# Connectors.net
KiCad netlist of a schematic drawn in Altium Designer
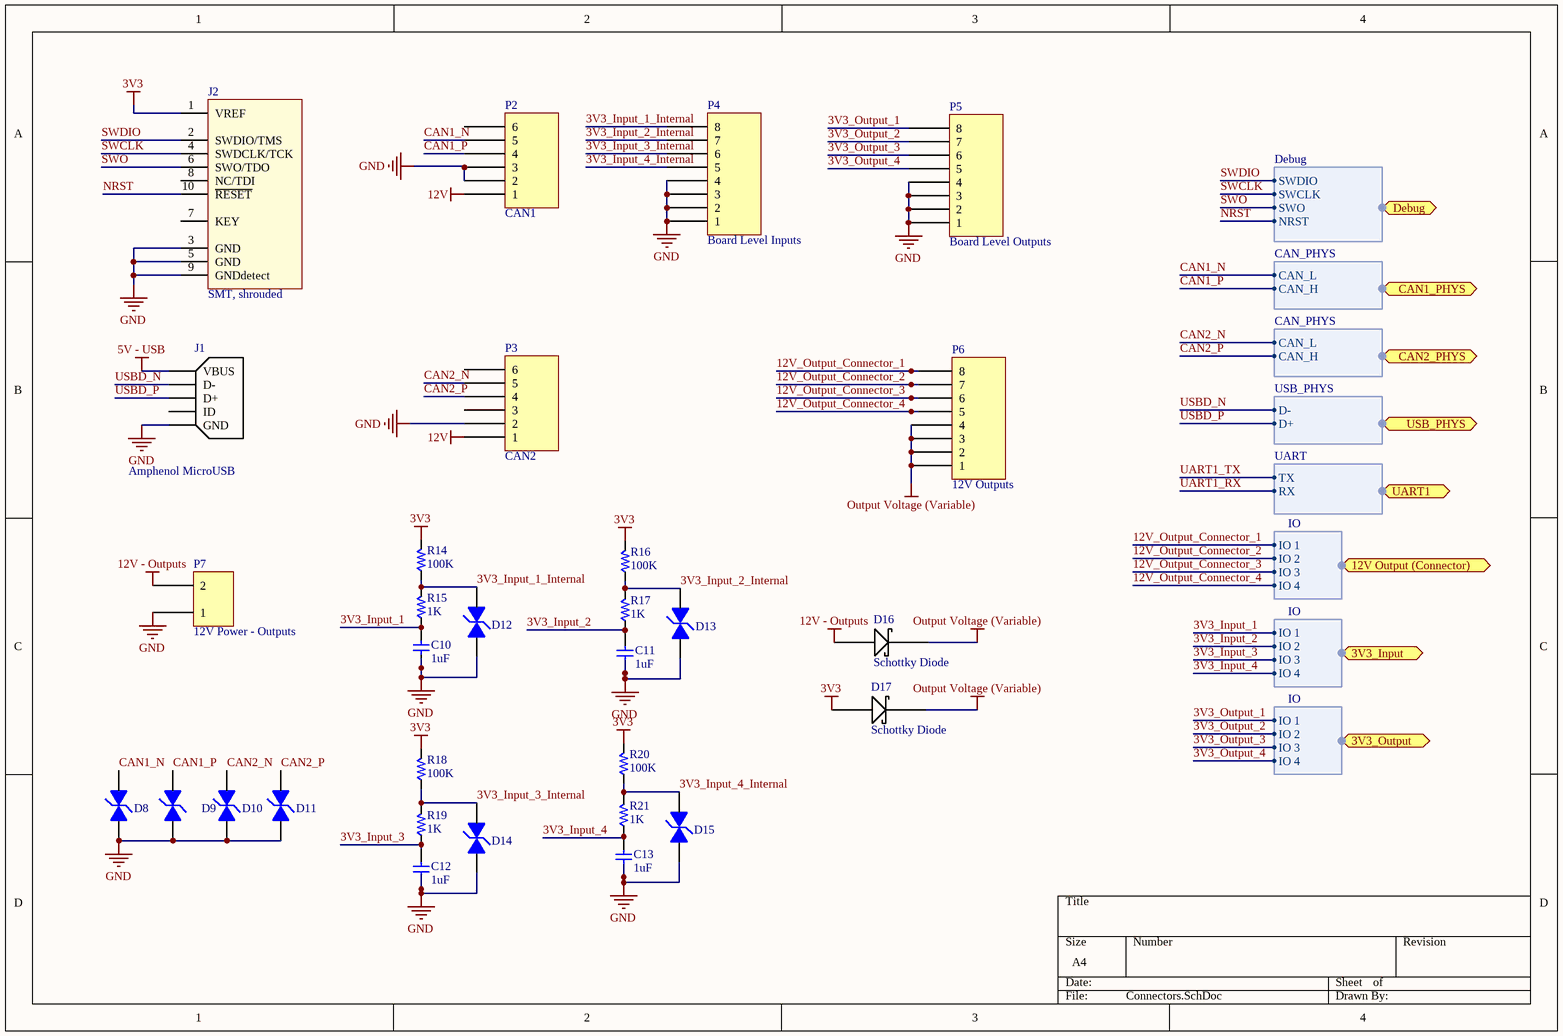
[diagram p0: Connectors.SchDoc]

(export (version "E")
  (design (tool "Eeschema 10.0.6"))
  (components
    (comp (ref "C10")
      (value "1uF")
      (footprint "PCB_GENERIC_SMD_0603")
      (description "CAP CER 0603 1uF 16V X5R 20%")
      (fields (field (name "TOLERANCE") "20%") (field (name "VOLTAGE") "16V"))
      (libsource (lib "CAP-0603") (part "C060-0001U-00"))
    )
    (comp (ref "C11")
      (value "1uF")
      (footprint "PCB_GENERIC_SMD_0603")
      (description "CAP CER 0603 1uF 16V X5R 20%")
      (fields (field (name "TOLERANCE") "20%") (field (name "VOLTAGE") "16V"))
      (libsource (lib "CAP-0603") (part "C060-0001U-00"))
    )
    (comp (ref "C12")
      (value "1uF")
      (footprint "PCB_GENERIC_SMD_0603")
      (description "CAP CER 0603 1uF 16V X5R 20%")
      (fields (field (name "TOLERANCE") "20%") (field (name "VOLTAGE") "16V"))
      (libsource (lib "CAP-0603") (part "C060-0001U-00"))
    )
    (comp (ref "C13")
      (value "1uF")
      (footprint "PCB_GENERIC_SMD_0603")
      (description "CAP CER 0603 1uF 16V X5R 20%")
      (fields (field (name "TOLERANCE") "20%") (field (name "VOLTAGE") "16V"))
      (libsource (lib "CAP-0603") (part "C060-0001U-00"))
    )
    (comp (ref "D8")
      (value "TVS Diode")
      (footprint "TVS Diode")
      (fields (field (name "MANUFACTURER") "Bourns"))
      (libsource (lib "TVS Diode") (part "TVS Diode"))
    )
    (comp (ref "D9")
      (value "TVS Diode")
      (footprint "TVS Diode")
      (fields (field (name "MANUFACTURER") "Bourns"))
      (libsource (lib "TVS Diode") (part "TVS Diode"))
    )
    (comp (ref "D10")
      (value "TVS Diode")
      (footprint "TVS Diode")
      (fields (field (name "MANUFACTURER") "Bourns"))
      (libsource (lib "TVS Diode") (part "TVS Diode"))
    )
    (comp (ref "D11")
      (value "TVS Diode")
      (footprint "TVS Diode")
      (fields (field (name "MANUFACTURER") "Bourns"))
      (libsource (lib "TVS Diode") (part "TVS Diode"))
    )
    (comp (ref "D12")
      (value "TVS Diode")
      (footprint "TVS Diode")
      (fields (field (name "MANUFACTURER") "Bourns"))
      (libsource (lib "TVS Diode") (part "TVS Diode"))
    )
    (comp (ref "D13")
      (value "TVS Diode")
      (footprint "TVS Diode")
      (fields (field (name "MANUFACTURER") "Bourns"))
      (libsource (lib "TVS Diode") (part "TVS Diode"))
    )
    (comp (ref "D14")
      (value "TVS Diode")
      (footprint "TVS Diode")
      (fields (field (name "MANUFACTURER") "Bourns"))
      (libsource (lib "TVS Diode") (part "TVS Diode"))
    )
    (comp (ref "D15")
      (value "TVS Diode")
      (footprint "TVS Diode")
      (fields (field (name "MANUFACTURER") "Bourns"))
      (libsource (lib "TVS Diode") (part "TVS Diode"))
    )
    (comp (ref "D16")
      (value "Schottky Diode")
      (footprint "ON Semi Schottky Diode - MBRM110LT1G")
      (libsource (lib "ON Semi Schottky Diode") (part "ON Semi Schottky Diode - MBRM110LT1G"))
    )
    (comp (ref "D17")
      (value "Schottky Diode")
      (footprint "ON Semi Schottky Diode - MBRM110LT1G")
      (libsource (lib "ON Semi Schottky Diode") (part "ON Semi Schottky Diode - MBRM110LT1G"))
    )
    (comp (ref "J1")
      (value "Amphenol MicroUSB")
      (footprint "Amphenol MicroUSB")
      (libsource (lib "Amphenol MicroUSB") (part "Amphenol MicroUSB - 609-4618-1-ND"))
    )
    (comp (ref "J2")
      (value "SMT, shrouded")
      (footprint "CONN-50mil-10POS-SMD")
      (description "ARM Cortex-M 10pin connector,shrouded,SMT")
      (libsource (lib "CONN-50mil-cortexM") (part "conn_0.050{dblquote}_cortexM"))
    )
    (comp (ref "P2")
      (value "CAN1")
      (footprint "Molex Microfit 3.0 3x2:PCB_MLX_MICROFIT_3X2")
      (libsource (lib "Molex Microfit 3.0 3x2") (part "SCH_MLX_MICROFIT_3X2"))
    )
    (comp (ref "P3")
      (value "CAN2")
      (footprint "Molex Microfit 3.0 3x2:PCB_MLX_MICROFIT_3X2")
      (libsource (lib "Molex Microfit 3.0 3x2") (part "SCH_MLX_MICROFIT_3X2"))
    )
    (comp (ref "P4")
      (value "Board Level Inputs")
      (footprint "Molex Microfit 3.0 4x2:PCB_MLX_MICROFIT_4X2")
      (description "Molex Microfit Connector 4x2")
      (libsource (lib "Molex Microfit 3.0 4x2") (part "SCH_MLX_MICROFIT_4X2"))
    )
    (comp (ref "P5")
      (value "Board Level Outputs")
      (footprint "Molex Microfit 3.0 4x2:PCB_MLX_MICROFIT_4X2")
      (description "Molex Microfit Connector 4x2")
      (libsource (lib "Molex Microfit 3.0 4x2") (part "SCH_MLX_MICROFIT_4X2"))
    )
    (comp (ref "P6")
      (value "12V Outputs")
      (footprint "Molex Microfit 3.0 4x2:PCB_MLX_MICROFIT_4X2")
      (description "Molex Microfit Connector 4x2")
      (libsource (lib "Molex Microfit 3.0 4x2") (part "SCH_MLX_MICROFIT_4X2"))
    )
    (comp (ref "P7")
      (value "12V Power - Outputs")
      (footprint "Molex Mini-Fit Jr 2x1")
      (libsource (lib "Molex Mini-Fit Jr 1x2") (part "Molex Mini-Fit 1x2"))
    )
    (comp (ref "R14")
      (value "100K")
      (footprint "PCB_GENERIC_SMD_0603")
      (description "RES 0603 100K 5% 63mW")
      (fields (field (name "TOLERANCE") "5%") (field (name "POWER") "63mW"))
      (libsource (lib "RES-0603") (part "R060-00104-05"))
    )
    (comp (ref "R15")
      (value "1K")
      (footprint "PCB_GENERIC_SMD_0603")
      (description "RES 0603 1K 5% 63mW")
      (fields (field (name "TOLERANCE") "5%") (field (name "POWER") "63mW"))
      (libsource (lib "RES-0603") (part "R060-00102-05"))
    )
    (comp (ref "R16")
      (value "100K")
      (footprint "PCB_GENERIC_SMD_0603")
      (description "RES 0603 100K 5% 63mW")
      (fields (field (name "TOLERANCE") "5%") (field (name "POWER") "63mW"))
      (libsource (lib "RES-0603") (part "R060-00104-05"))
    )
    (comp (ref "R17")
      (value "1K")
      (footprint "PCB_GENERIC_SMD_0603")
      (description "RES 0603 1K 5% 63mW")
      (fields (field (name "TOLERANCE") "5%") (field (name "POWER") "63mW"))
      (libsource (lib "RES-0603") (part "R060-00102-05"))
    )
    (comp (ref "R18")
      (value "100K")
      (footprint "PCB_GENERIC_SMD_0603")
      (description "RES 0603 100K 5% 63mW")
      (fields (field (name "TOLERANCE") "5%") (field (name "POWER") "63mW"))
      (libsource (lib "RES-0603") (part "R060-00104-05"))
    )
    (comp (ref "R19")
      (value "1K")
      (footprint "PCB_GENERIC_SMD_0603")
      (description "RES 0603 1K 5% 63mW")
      (fields (field (name "TOLERANCE") "5%") (field (name "POWER") "63mW"))
      (libsource (lib "RES-0603") (part "R060-00102-05"))
    )
    (comp (ref "R20")
      (value "100K")
      (footprint "PCB_GENERIC_SMD_0603")
      (description "RES 0603 100K 5% 63mW")
      (fields (field (name "TOLERANCE") "5%") (field (name "POWER") "63mW"))
      (libsource (lib "RES-0603") (part "R060-00104-05"))
    )
    (comp (ref "R21")
      (value "1K")
      (footprint "PCB_GENERIC_SMD_0603")
      (description "RES 0603 1K 5% 63mW")
      (fields (field (name "TOLERANCE") "5%") (field (name "POWER") "63mW"))
      (libsource (lib "RES-0603") (part "R060-00102-05"))
    )
  )
  (nets
    (net (code "6") (name "/3V3_Input_1") (class "Default")
      (node (ref "C10") (pin "2") (pinfunction "2_2") (pintype "passive"))
      (node (ref "R15") (pin "1") (pinfunction "1_1") (pintype "passive"))
    )
    (net (code "7") (name "/3V3_Input_1_Internal") (class "Default")
      (node (ref "D12") (pin "1") (pintype "passive"))
      (node (ref "P4") (pin "8") (pinfunction "8_8") (pintype "passive"))
      (node (ref "R14") (pin "1") (pinfunction "1_1") (pintype "passive"))
      (node (ref "R15") (pin "2") (pinfunction "2_2") (pintype "passive"))
    )
    (net (code "8") (name "/3V3_Input_2") (class "Default")
      (node (ref "C11") (pin "2") (pinfunction "2_2") (pintype "passive"))
      (node (ref "R17") (pin "1") (pinfunction "1_1") (pintype "passive"))
    )
    (net (code "9") (name "/3V3_Input_2_Internal") (class "Default")
      (node (ref "D13") (pin "1") (pintype "passive"))
      (node (ref "P4") (pin "7") (pinfunction "7_7") (pintype "passive"))
      (node (ref "R16") (pin "1") (pinfunction "1_1") (pintype "passive"))
      (node (ref "R17") (pin "2") (pinfunction "2_2") (pintype "passive"))
    )
    (net (code "10") (name "/3V3_Input_3") (class "Default")
      (node (ref "C12") (pin "2") (pinfunction "2_2") (pintype "passive"))
      (node (ref "R19") (pin "1") (pinfunction "1_1") (pintype "passive"))
    )
    (net (code "11") (name "/3V3_Input_3_Internal") (class "Default")
      (node (ref "D14") (pin "1") (pintype "passive"))
      (node (ref "P4") (pin "6") (pinfunction "6_6") (pintype "passive"))
      (node (ref "R18") (pin "1") (pinfunction "1_1") (pintype "passive"))
      (node (ref "R19") (pin "2") (pinfunction "2_2") (pintype "passive"))
    )
    (net (code "12") (name "/3V3_Input_4") (class "Default")
      (node (ref "C13") (pin "2") (pinfunction "2_2") (pintype "passive"))
      (node (ref "R21") (pin "1") (pinfunction "1_1") (pintype "passive"))
    )
    (net (code "13") (name "/3V3_Input_4_Internal") (class "Default")
      (node (ref "D15") (pin "1") (pintype "passive"))
      (node (ref "P4") (pin "5") (pinfunction "5_5") (pintype "passive"))
      (node (ref "R20") (pin "1") (pinfunction "1_1") (pintype "passive"))
    )
    (net (code "14") (name "/3V3_Output_1") (class "Default")
      (node (ref "P5") (pin "8") (pinfunction "8_8") (pintype "passive"))
    )
    (net (code "15") (name "/3V3_Output_2") (class "Default")
      (node (ref "P5") (pin "7") (pinfunction "7_7") (pintype "passive"))
    )
    (net (code "16") (name "/3V3_Output_3") (class "Default")
      (node (ref "P5") (pin "6") (pinfunction "6_6") (pintype "passive"))
    )
    (net (code "17") (name "/3V3_Output_4") (class "Default")
      (node (ref "P5") (pin "5") (pinfunction "5_5") (pintype "passive"))
    )
    (net (code "18") (name "/12V_Output_Connector_1") (class "Default")
      (node (ref "P6") (pin "8") (pinfunction "8_8") (pintype "passive"))
    )
    (net (code "19") (name "/12V_Output_Connector_2") (class "Default")
      (node (ref "P6") (pin "7") (pinfunction "7_7") (pintype "passive"))
    )
    (net (code "20") (name "/12V_Output_Connector_3") (class "Default")
      (node (ref "P6") (pin "6") (pinfunction "6_6") (pintype "passive"))
    )
    (net (code "21") (name "/12V_Output_Connector_4") (class "Default")
      (node (ref "P6") (pin "5") (pinfunction "5_5") (pintype "passive"))
    )
    (net (code "22") (name "/CAN1_N") (class "Default")
      (node (ref "D8") (pin "1") (pintype "passive"))
      (node (ref "P2") (pin "5") (pinfunction "5_5") (pintype "passive"))
    )
    (net (code "23") (name "/CAN1_P") (class "Default")
      (node (ref "D9") (pin "1") (pintype "passive"))
      (node (ref "P2") (pin "4") (pinfunction "4_4") (pintype "passive"))
    )
    (net (code "24") (name "/CAN2_N") (class "Default")
      (node (ref "D10") (pin "1") (pintype "passive"))
      (node (ref "P3") (pin "5") (pinfunction "5_5") (pintype "passive"))
    )
    (net (code "25") (name "/CAN2_P") (class "Default")
      (node (ref "D11") (pin "1") (pintype "passive"))
      (node (ref "P3") (pin "4") (pinfunction "4_4") (pintype "passive"))
    )
    (net (code "26") (name "/NRST") (class "Default")
      (node (ref "J2") (pin "10") (pinfunction "~{RESET}_10") (pintype "passive"))
    )
    (net (code "27") (name "/SWCLK") (class "Default")
      (node (ref "J2") (pin "4") (pinfunction "SWDCLK/TCK_4") (pintype "passive"))
    )
    (net (code "28") (name "/SWDIO") (class "Default")
      (node (ref "J2") (pin "2") (pinfunction "SWDIO/TMS_2") (pintype "passive"))
    )
    (net (code "29") (name "/SWO") (class "Default")
      (node (ref "J2") (pin "6") (pinfunction "SWO/TDO_6") (pintype "passive"))
    )
    (net (code "32") (name "/USBD_N") (class "Default")
      (node (ref "J1") (pin "2") (pinfunction "D-_2") (pintype "passive"))
    )
    (net (code "33") (name "/USBD_P") (class "Default")
      (node (ref "J1") (pin "3") (pinfunction "D+_3") (pintype "passive"))
    )
    (net (code "39") (name "3V3") (class "Default")
      (node (ref "D17") (pin "2") (pinfunction "2_2") (pintype "passive"))
      (node (ref "J2") (pin "1") (pinfunction "VREF_1") (pintype "passive"))
      (node (ref "R14") (pin "2") (pinfunction "2_2") (pintype "passive"))
      (node (ref "R16") (pin "2") (pinfunction "2_2") (pintype "passive"))
      (node (ref "R18") (pin "2") (pinfunction "2_2") (pintype "passive"))
      (node (ref "R20") (pin "2") (pinfunction "2_2") (pintype "passive"))
    )
    (net (code "40") (name "5V - USB") (class "Default")
      (node (ref "J1") (pin "1") (pinfunction "VBUS_1") (pintype "passive"))
    )
    (net (code "41") (name "12V") (class "Default")
      (node (ref "P2") (pin "1") (pinfunction "1_1") (pintype "passive"))
      (node (ref "P3") (pin "1") (pinfunction "1_1") (pintype "passive"))
    )
    (net (code "42") (name "12V - Outputs") (class "Default")
      (node (ref "D16") (pin "2") (pinfunction "2_2") (pintype "passive"))
      (node (ref "P7") (pin "2") (pinfunction "2_2") (pintype "passive"))
    )
    (net (code "43") (name "GND") (class "Default")
      (node (ref "C10") (pin "1") (pinfunction "1_1") (pintype "passive"))
      (node (ref "C11") (pin "1") (pinfunction "1_1") (pintype "passive"))
      (node (ref "C12") (pin "1") (pinfunction "1_1") (pintype "passive"))
      (node (ref "C13") (pin "1") (pinfunction "1_1") (pintype "passive"))
      (node (ref "D10") (pin "2") (pintype "passive"))
      (node (ref "D11") (pin "2") (pintype "passive"))
      (node (ref "D12") (pin "2") (pintype "passive"))
      (node (ref "D13") (pin "2") (pintype "passive"))
      (node (ref "D14") (pin "2") (pintype "passive"))
      (node (ref "D15") (pin "2") (pintype "passive"))
      (node (ref "D8") (pin "2") (pintype "passive"))
      (node (ref "D9") (pin "2") (pintype "passive"))
      (node (ref "J1") (pin "5") (pinfunction "GND_5") (pintype "passive"))
      (node (ref "J2") (pin "3") (pinfunction "GND_3") (pintype "passive"))
      (node (ref "J2") (pin "5") (pinfunction "GND_5") (pintype "passive"))
      (node (ref "J2") (pin "9") (pinfunction "GNDdetect_9") (pintype "passive"))
      (node (ref "P2") (pin "2") (pinfunction "2_2") (pintype "passive"))
      (node (ref "P2") (pin "3") (pinfunction "3_3") (pintype "passive"))
      (node (ref "P3") (pin "2") (pinfunction "2_2") (pintype "passive"))
      (node (ref "P4") (pin "1") (pinfunction "1_1") (pintype "passive"))
      (node (ref "P4") (pin "2") (pinfunction "2_2") (pintype "passive"))
      (node (ref "P4") (pin "3") (pinfunction "3_3") (pintype "passive"))
      (node (ref "P4") (pin "4") (pinfunction "4_4") (pintype "passive"))
      (node (ref "P5") (pin "1") (pinfunction "1_1") (pintype "passive"))
      (node (ref "P5") (pin "2") (pinfunction "2_2") (pintype "passive"))
      (node (ref "P5") (pin "3") (pinfunction "3_3") (pintype "passive"))
      (node (ref "P5") (pin "4") (pinfunction "4_4") (pintype "passive"))
      (node (ref "P7") (pin "1") (pinfunction "1_1") (pintype "passive"))
    )
    (net (code "44") (name "Output Voltage (Variable)") (class "Default")
      (node (ref "D16") (pin "1") (pinfunction "1_1") (pintype "passive"))
      (node (ref "D17") (pin "1") (pinfunction "1_1") (pintype "passive"))
      (node (ref "P6") (pin "1") (pinfunction "1_1") (pintype "passive"))
      (node (ref "P6") (pin "2") (pinfunction "2_2") (pintype "passive"))
      (node (ref "P6") (pin "3") (pinfunction "3_3") (pintype "passive"))
      (node (ref "P6") (pin "4") (pinfunction "4_4") (pintype "passive"))
    )
    (net (code "45") (name "unconnected-(J1-ID-Pad4)") (class "Default")
      (node (ref "J1") (pin "4") (pinfunction "ID_4") (pintype "passive"))
    )
    (net (code "46") (name "unconnected-(J2-KEY-Pad7)") (class "Default")
      (node (ref "J2") (pin "7") (pinfunction "KEY_7") (pintype "passive"))
    )
    (net (code "47") (name "unconnected-(J2-NC{slash}TDI-Pad8)") (class "Default")
      (node (ref "J2") (pin "8") (pinfunction "NC/TDI_8") (pintype "passive"))
    )
    (net (code "48") (name "unconnected-(P2-Pad6)") (class "Default")
      (node (ref "P2") (pin "6") (pinfunction "6_6") (pintype "passive"))
    )
    (net (code "49") (name "unconnected-(P3-Pad3)") (class "Default")
      (node (ref "P3") (pin "3") (pinfunction "3_3") (pintype "passive"))
    )
    (net (code "50") (name "unconnected-(P3-Pad6)") (class "Default")
      (node (ref "P3") (pin "6") (pinfunction "6_6") (pintype "passive"))
    )
    (net (code "51") (name "unconnected-(R21-Pad2)") (class "Default")
      (node (ref "R21") (pin "2") (pinfunction "2_2") (pintype "passive"))
    )
  )
)
